# MCU.net
KiCad netlist of a schematic drawn in Altium Designer
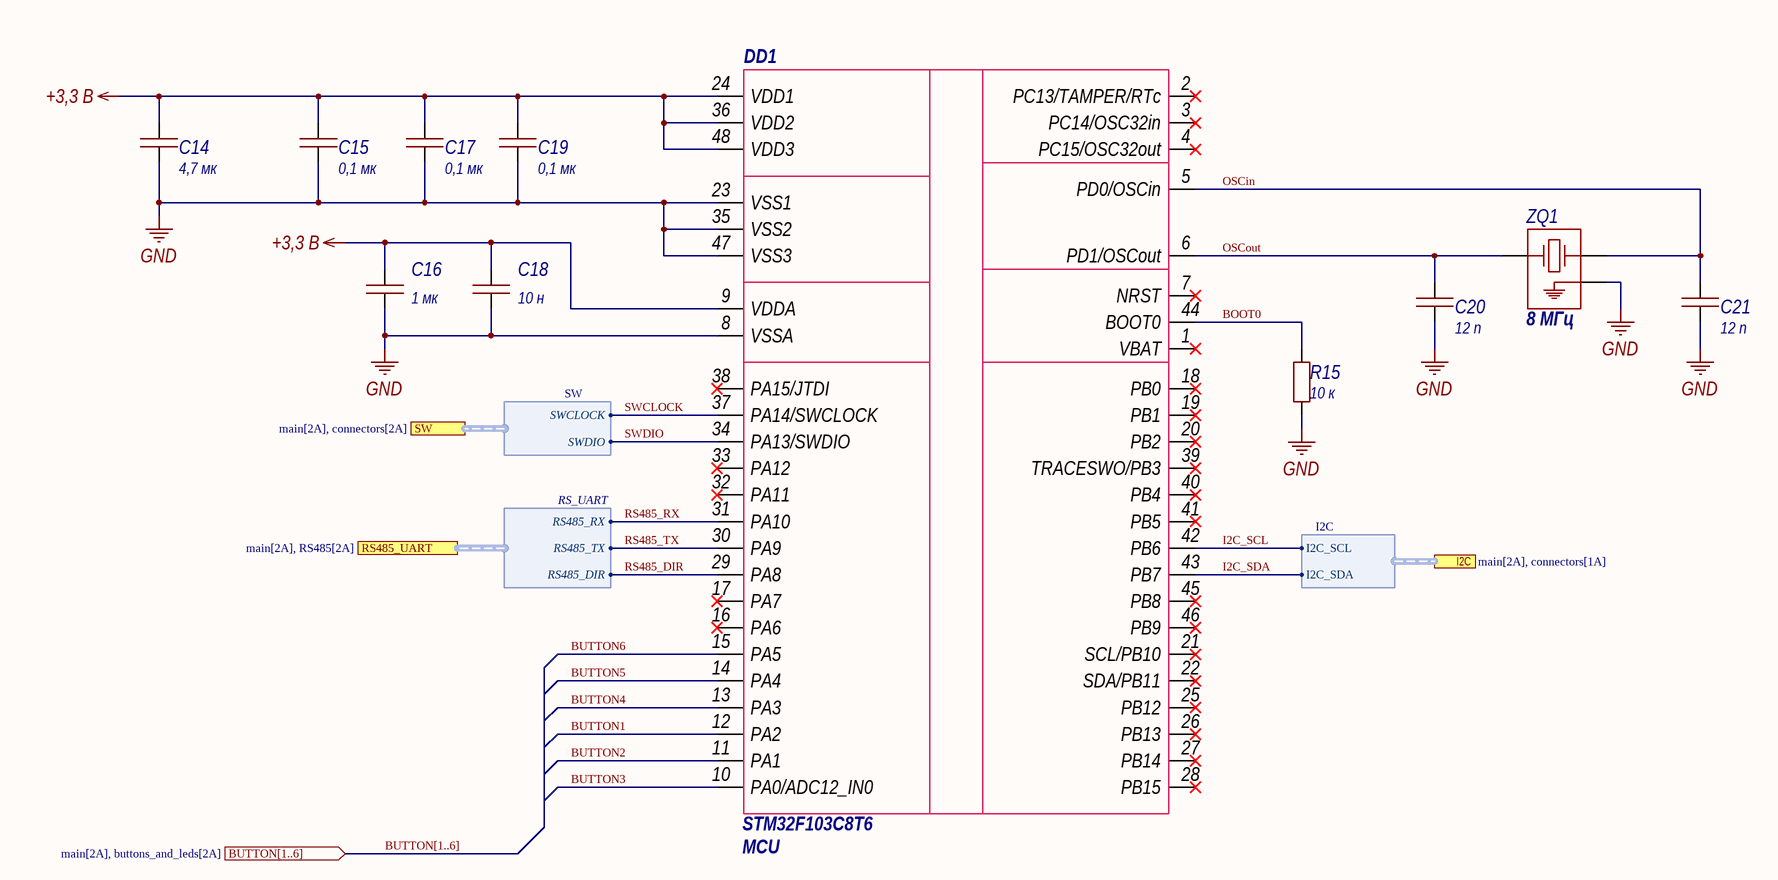
[diagram p0: MCU.SchDoc]

(export (version "E")
  (design (tool "Eeschema 10.0.6"))
  (components
    (comp (ref "C14")
      (value "4,7 мк")
      (footprint "1206C")
      (description "Конденсатор 1206C ёмкостью 4,7 мк 10%, 50 В, X7R")
      (fields (field (name "PART NUMBER") "Capacitor_4,7u_10_50V_X7R_1206C") (field (name "TOLERANCE") "10%"))
      (libsource (lib "Hydrolib") (part "Capacitor"))
    )
    (comp (ref "C15")
      (value "0,1 мк")
      (footprint "0603C")
      (description "Конденсатор 0603C ёмкостью 0,1 мк 10%, 50 В, X7R")
      (fields (field (name "PART NUMBER") "Capacitor_0,1u_10_50V_X7R_0603C") (field (name "TOLERANCE") "10%"))
      (libsource (lib "Hydrolib") (part "Capacitor"))
    )
    (comp (ref "C16")
      (value "1 мк")
      (footprint "0603C")
      (description "Конденсатор 0603C ёмкостью 1 мк 10%, 50 В, X7R")
      (fields (field (name "PART NUMBER") "Capacitor_1u_10_50V_X7R_0603C") (field (name "TOLERANCE") "10%"))
      (libsource (lib "Hydrolib") (part "Capacitor"))
    )
    (comp (ref "C17")
      (value "0,1 мк")
      (footprint "0603C")
      (description "Конденсатор 0603C ёмкостью 0,1 мк 10%, 50 В, X7R")
      (fields (field (name "PART NUMBER") "Capacitor_0,1u_10_50V_X7R_0603C") (field (name "TOLERANCE") "10%"))
      (libsource (lib "Hydrolib") (part "Capacitor"))
    )
    (comp (ref "C18")
      (value "10 н")
      (footprint "0603C")
      (description "Конденсатор 0603C ёмкостью 10 н 10%, 50 В, X7R")
      (fields (field (name "PART NUMBER") "Capacitor_10n_10_50V_X7R_0603C") (field (name "TOLERANCE") "10%"))
      (libsource (lib "Hydrolib") (part "Capacitor"))
    )
    (comp (ref "C19")
      (value "0,1 мк")
      (footprint "0603C")
      (description "Конденсатор 0603C ёмкостью 0,1 мк 10%, 50 В, X7R")
      (fields (field (name "PART NUMBER") "Capacitor_0,1u_10_50V_X7R_0603C") (field (name "TOLERANCE") "10%"))
      (libsource (lib "Hydrolib") (part "Capacitor"))
    )
    (comp (ref "C20")
      (value "12 п")
      (footprint "0603C")
      (description "Конденсатор 12п")
      (fields (field (name "PART NUMBER") "Capacitor"))
      (libsource (lib "Hydrolib") (part "Capacitor"))
    )
    (comp (ref "C21")
      (value "12 п")
      (footprint "0603C")
      (description "Конденсатор 12п")
      (fields (field (name "PART NUMBER") "Capacitor"))
      (libsource (lib "Hydrolib") (part "Capacitor"))
    )
    (comp (ref "DD1")
      (value "STM32F103C8T6")
      (footprint "LQFP48")
      (description "Микроконтроллер")
      (fields (field (name "MANUFACTURER") "ST Microelectronics") (field (name "VALUE1") "MCU"))
      (libsource (lib "Hydrolib") (part "STM32F103C8T6"))
    )
    (comp (ref "R15")
      (value "10 к")
      (footprint "0603R")
      (description "Резистор номиналом 10 кОм 1%")
      (fields (field (name "PART NUMBER") "Resistor_10k_1_0603") (field (name "TOLERANCE") "1%"))
      (libsource (lib "Hydrolib") (part "Resistor"))
    )
    (comp (ref "ZQ1")
      (value "8 МГц")
      (footprint "QSMD3.2x2.5")
      (description "Кварцевый резонатор с входом земли")
      (fields (field (name "PART NUMBER") "XTAL_GND"))
      (libsource (lib "Hydrolib") (part "XTAL_GND"))
    )
  )
  (nets
    (net (code "4") (name "+3,3 В") (class "Default")
      (node (ref "C14") (pin "2") (pinfunction "2_2") (pintype "passive"))
      (node (ref "C15") (pin "2") (pinfunction "2_2") (pintype "passive"))
      (node (ref "C16") (pin "2") (pinfunction "2_2") (pintype "passive"))
      (node (ref "C17") (pin "2") (pinfunction "2_2") (pintype "passive"))
      (node (ref "C18") (pin "2") (pinfunction "2_2") (pintype "passive"))
      (node (ref "C19") (pin "2") (pinfunction "2_2") (pintype "passive"))
      (node (ref "DD1") (pin "24") (pinfunction "VDD1_24") (pintype "passive"))
      (node (ref "DD1") (pin "36") (pinfunction "VDD2_36") (pintype "passive"))
      (node (ref "DD1") (pin "48") (pinfunction "VDD3_48") (pintype "passive"))
      (node (ref "DD1") (pin "9") (pinfunction "VDDA_9") (pintype "passive"))
    )
    (net (code "5") (name "/BOOT0") (class "Default")
      (node (ref "DD1") (pin "44") (pinfunction "BOOT0_44") (pintype "passive"))
      (node (ref "R15") (pin "2") (pinfunction "2_2") (pintype "passive"))
    )
    (net (code "6") (name "/BUTTON1") (class "Default")
      (node (ref "DD1") (pin "12") (pinfunction "PA2_12") (pintype "passive"))
    )
    (net (code "7") (name "/BUTTON2") (class "Default")
      (node (ref "DD1") (pin "11") (pinfunction "PA1_11") (pintype "passive"))
    )
    (net (code "8") (name "/BUTTON3") (class "Default")
      (node (ref "DD1") (pin "10") (pinfunction "PA0/ADC12_IN0_10") (pintype "passive"))
    )
    (net (code "9") (name "/BUTTON4") (class "Default")
      (node (ref "DD1") (pin "13") (pinfunction "PA3_13") (pintype "passive"))
    )
    (net (code "10") (name "/BUTTON5") (class "Default")
      (node (ref "DD1") (pin "14") (pinfunction "PA4_14") (pintype "passive"))
    )
    (net (code "11") (name "/BUTTON6") (class "Default")
      (node (ref "DD1") (pin "15") (pinfunction "PA5_15") (pintype "passive"))
    )
    (net (code "13") (name "/I2C_SCL") (class "Default")
      (node (ref "DD1") (pin "42") (pinfunction "PB6_42") (pintype "passive"))
    )
    (net (code "14") (name "/I2C_SDA") (class "Default")
      (node (ref "DD1") (pin "43") (pinfunction "PB7_43") (pintype "passive"))
    )
    (net (code "15") (name "/OSCin") (class "Default")
      (node (ref "C21") (pin "2") (pinfunction "2_2") (pintype "passive"))
      (node (ref "DD1") (pin "5") (pinfunction "PD0/OSCin_5") (pintype "passive"))
      (node (ref "ZQ1") (pin "2") (pinfunction "2_2") (pintype "passive"))
    )
    (net (code "16") (name "/OSCout") (class "Default")
      (node (ref "C20") (pin "2") (pinfunction "2_2") (pintype "passive"))
      (node (ref "DD1") (pin "6") (pinfunction "PD1/OSCout_6") (pintype "passive"))
      (node (ref "ZQ1") (pin "1") (pinfunction "1_1") (pintype "passive"))
    )
    (net (code "17") (name "/RS485_DIR") (class "Default")
      (node (ref "DD1") (pin "29") (pinfunction "PA8_29") (pintype "passive"))
    )
    (net (code "18") (name "/RS485_RX") (class "Default")
      (node (ref "DD1") (pin "31") (pinfunction "PA10_31") (pintype "passive"))
    )
    (net (code "19") (name "/RS485_TX") (class "Default")
      (node (ref "DD1") (pin "30") (pinfunction "PA9_30") (pintype "passive"))
    )
    (net (code "20") (name "/SWCLOCK") (class "Default")
      (node (ref "DD1") (pin "37") (pinfunction "PA14/SWCLOCK_37") (pintype "passive"))
    )
    (net (code "21") (name "/SWDIO") (class "Default")
      (node (ref "DD1") (pin "34") (pinfunction "PA13/SWDIO_34") (pintype "passive"))
    )
    (net (code "25") (name "GND") (class "Default")
      (node (ref "C14") (pin "1") (pinfunction "1_1") (pintype "passive"))
      (node (ref "C15") (pin "1") (pinfunction "1_1") (pintype "passive"))
      (node (ref "C16") (pin "1") (pinfunction "1_1") (pintype "passive"))
      (node (ref "C17") (pin "1") (pinfunction "1_1") (pintype "passive"))
      (node (ref "C18") (pin "1") (pinfunction "1_1") (pintype "passive"))
      (node (ref "C19") (pin "1") (pinfunction "1_1") (pintype "passive"))
      (node (ref "C20") (pin "1") (pinfunction "1_1") (pintype "passive"))
      (node (ref "C21") (pin "1") (pinfunction "1_1") (pintype "passive"))
      (node (ref "DD1") (pin "23") (pinfunction "VSS1_23") (pintype "passive"))
      (node (ref "DD1") (pin "35") (pinfunction "VSS2_35") (pintype "passive"))
      (node (ref "DD1") (pin "47") (pinfunction "VSS3_47") (pintype "passive"))
      (node (ref "DD1") (pin "8") (pinfunction "VSSA_8") (pintype "passive"))
      (node (ref "R15") (pin "1") (pinfunction "1_1") (pintype "passive"))
      (node (ref "ZQ1") (pin "3") (pinfunction "3_3") (pintype "passive"))
    )
    (net (code "26") (name "unconnected-(DD1-NRST-Pad7)") (class "Default")
      (node (ref "DD1") (pin "7") (pinfunction "NRST_7") (pintype "passive+no_connect"))
    )
    (net (code "27") (name "unconnected-(DD1-PA6-Pad16)") (class "Default")
      (node (ref "DD1") (pin "16") (pinfunction "PA6_16") (pintype "passive+no_connect"))
    )
    (net (code "28") (name "unconnected-(DD1-PA7-Pad17)") (class "Default")
      (node (ref "DD1") (pin "17") (pinfunction "PA7_17") (pintype "passive+no_connect"))
    )
    (net (code "29") (name "unconnected-(DD1-PA11-Pad32)") (class "Default")
      (node (ref "DD1") (pin "32") (pinfunction "PA11_32") (pintype "passive+no_connect"))
    )
    (net (code "30") (name "unconnected-(DD1-PA12-Pad33)") (class "Default")
      (node (ref "DD1") (pin "33") (pinfunction "PA12_33") (pintype "passive+no_connect"))
    )
    (net (code "31") (name "unconnected-(DD1-PA15{slash}JTDI-Pad38)") (class "Default")
      (node (ref "DD1") (pin "38") (pinfunction "PA15/JTDI_38") (pintype "passive+no_connect"))
    )
    (net (code "32") (name "unconnected-(DD1-PB0-Pad18)") (class "Default")
      (node (ref "DD1") (pin "18") (pinfunction "PB0_18") (pintype "passive+no_connect"))
    )
    (net (code "33") (name "unconnected-(DD1-PB1-Pad19)") (class "Default")
      (node (ref "DD1") (pin "19") (pinfunction "PB1_19") (pintype "passive+no_connect"))
    )
    (net (code "34") (name "unconnected-(DD1-PB2-Pad20)") (class "Default")
      (node (ref "DD1") (pin "20") (pinfunction "PB2_20") (pintype "passive+no_connect"))
    )
    (net (code "35") (name "unconnected-(DD1-PB4-Pad40)") (class "Default")
      (node (ref "DD1") (pin "40") (pinfunction "PB4_40") (pintype "passive+no_connect"))
    )
    (net (code "36") (name "unconnected-(DD1-PB5-Pad41)") (class "Default")
      (node (ref "DD1") (pin "41") (pinfunction "PB5_41") (pintype "passive+no_connect"))
    )
    (net (code "37") (name "unconnected-(DD1-PB8-Pad45)") (class "Default")
      (node (ref "DD1") (pin "45") (pinfunction "PB8_45") (pintype "passive+no_connect"))
    )
    (net (code "38") (name "unconnected-(DD1-PB9-Pad46)") (class "Default")
      (node (ref "DD1") (pin "46") (pinfunction "PB9_46") (pintype "passive+no_connect"))
    )
    (net (code "39") (name "unconnected-(DD1-PB12-Pad25)") (class "Default")
      (node (ref "DD1") (pin "25") (pinfunction "PB12_25") (pintype "passive+no_connect"))
    )
    (net (code "40") (name "unconnected-(DD1-PB13-Pad26)") (class "Default")
      (node (ref "DD1") (pin "26") (pinfunction "PB13_26") (pintype "passive+no_connect"))
    )
    (net (code "41") (name "unconnected-(DD1-PB14-Pad27)") (class "Default")
      (node (ref "DD1") (pin "27") (pinfunction "PB14_27") (pintype "passive+no_connect"))
    )
    (net (code "42") (name "unconnected-(DD1-PB15-Pad28)") (class "Default")
      (node (ref "DD1") (pin "28") (pinfunction "PB15_28") (pintype "passive+no_connect"))
    )
    (net (code "43") (name "unconnected-(DD1-PC13{slash}TAMPER{slash}RTc-Pad2)") (class "Default")
      (node (ref "DD1") (pin "2") (pinfunction "PC13/TAMPER/RTc_2") (pintype "passive+no_connect"))
    )
    (net (code "44") (name "unconnected-(DD1-PC14{slash}OSC32in-Pad3)") (class "Default")
      (node (ref "DD1") (pin "3") (pinfunction "PC14/OSC32in_3") (pintype "passive+no_connect"))
    )
    (net (code "45") (name "unconnected-(DD1-PC15{slash}OSC32out-Pad4)") (class "Default")
      (node (ref "DD1") (pin "4") (pinfunction "PC15/OSC32out_4") (pintype "passive+no_connect"))
    )
    (net (code "46") (name "unconnected-(DD1-SCL{slash}PB10-Pad21)") (class "Default")
      (node (ref "DD1") (pin "21") (pinfunction "SCL/PB10_21") (pintype "passive+no_connect"))
    )
    (net (code "47") (name "unconnected-(DD1-SDA{slash}PB11-Pad22)") (class "Default")
      (node (ref "DD1") (pin "22") (pinfunction "SDA/PB11_22") (pintype "passive+no_connect"))
    )
    (net (code "48") (name "unconnected-(DD1-TRACESWO{slash}PB3-Pad39)") (class "Default")
      (node (ref "DD1") (pin "39") (pinfunction "TRACESWO/PB3_39") (pintype "passive+no_connect"))
    )
    (net (code "49") (name "unconnected-(DD1-VBAT-Pad1)") (class "Default")
      (node (ref "DD1") (pin "1") (pinfunction "VBAT_1") (pintype "passive+no_connect"))
    )
  )
)
